# rc-light-controller.net
KiCad netlist of a schematic drawn in EAGLE
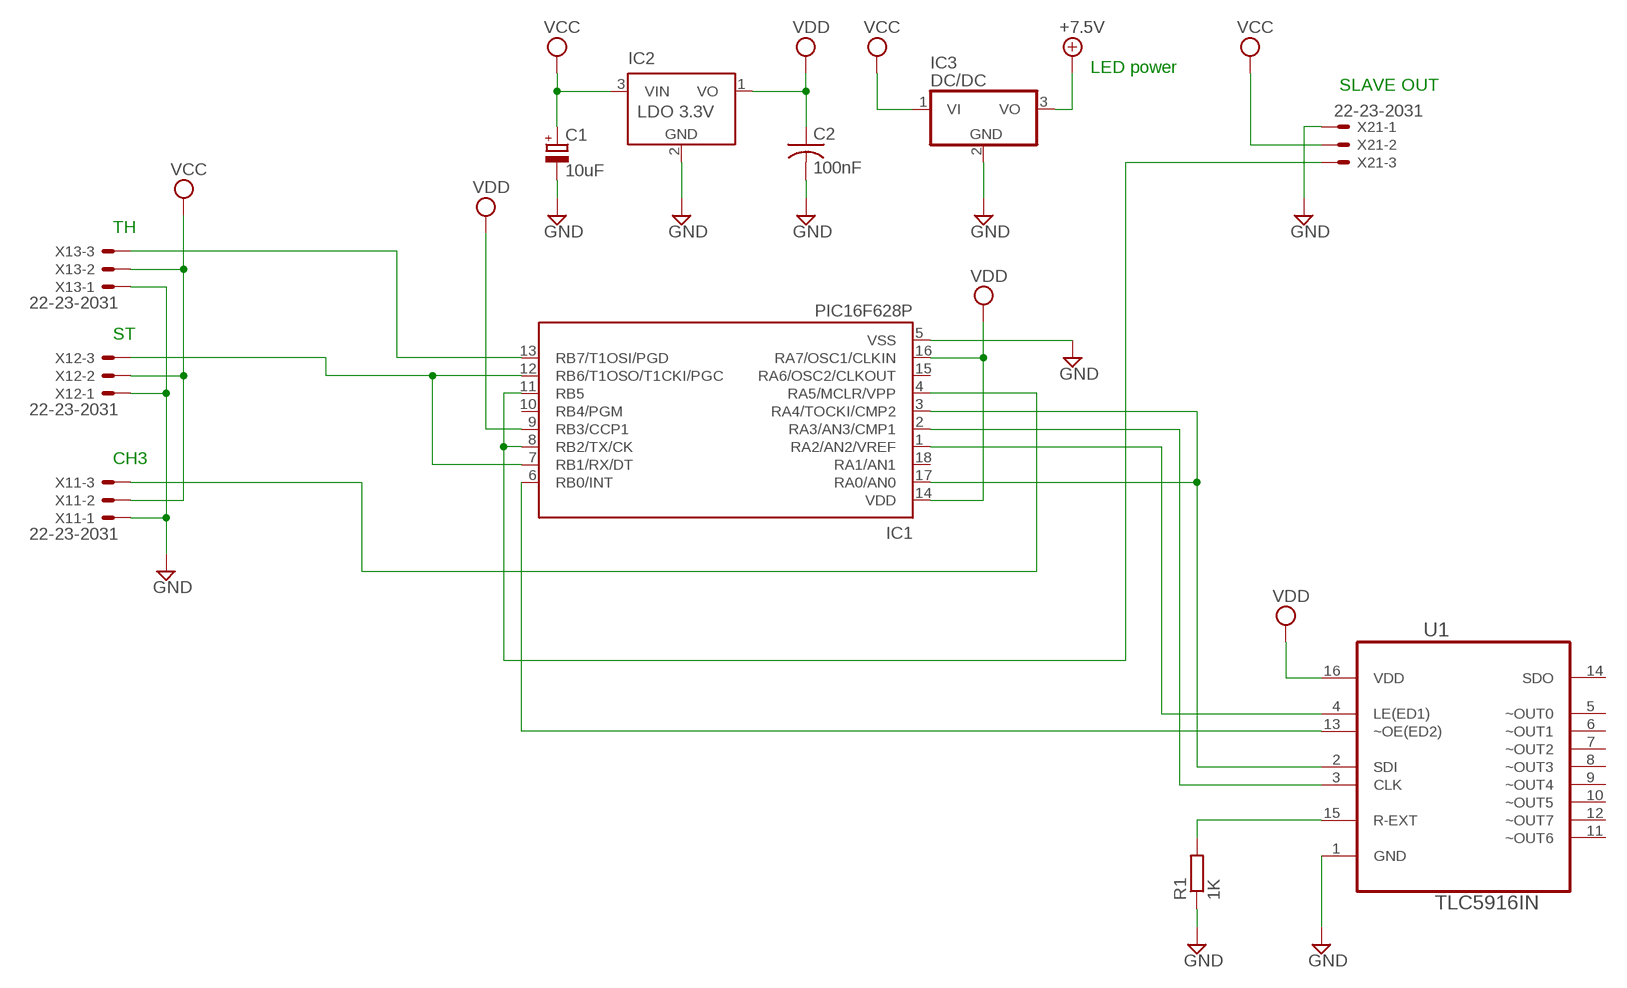
[diagram p0: schematic, sheet 1]

(export (version "E")
  (design (tool "Eeschema 10.0.6"))
  (components
    (comp (ref "C1")
      (value "10uF")
      (footprint "eagle-import:E5-5")
      (libsource (lib "eagle-import") (part "CPOL-EUE5-5"))
    )
    (comp (ref "C2")
      (value "100nF")
      (footprint "eagle-import:C025-025X050")
      (libsource (lib "eagle-import") (part "C-US025-025X050"))
    )
    (comp (ref "IC1")
      (value "PIC16F628P")
      (footprint "eagle-import:DIL18")
      (libsource (lib "eagle-import") (part "PIC16F62P8"))
    )
    (comp (ref "IC2")
      (value "LDO 3.3V")
      (footprint "eagle-import:TO92")
      (fields (field (name "MF") "NATIONAL SEMICONDUCTOR") (field (name "MPN") "LM2936Z-3.3/NOPB"))
      (libsource (lib "eagle-import") (part "LM2936?Z-3.3"))
    )
    (comp (ref "IC3")
      (value "DC/DC")
      (footprint "eagle-import:TO220H")
      (libsource (lib "eagle-import") (part "78T05"))
    )
    (comp (ref "R1")
      (value "1K")
      (footprint "eagle-import:0204_7")
      (libsource (lib "eagle-import") (part "R-EU_0204/7"))
    )
    (comp (ref "U1")
      (value "TLC5916IN")
      (footprint "eagle-import:DIP254P762X508-16")
      (libsource (lib "eagle-import") (part "TLC5916IN"))
    )
    (comp (ref "X11")
      (value "22-23-2031")
      (footprint "eagle-import:22-23-2031")
      (libsource (lib "eagle-import") (part "22-23-2031"))
    )
    (comp (ref "X12")
      (value "22-23-2031")
      (footprint "eagle-import:22-23-2031")
      (libsource (lib "eagle-import") (part "22-23-2031"))
    )
    (comp (ref "X13")
      (value "22-23-2031")
      (footprint "eagle-import:22-23-2031")
      (libsource (lib "eagle-import") (part "22-23-2031"))
    )
    (comp (ref "X21")
      (value "22-23-2031")
      (footprint "eagle-import:22-23-2031")
      (libsource (lib "eagle-import") (part "22-23-2031"))
    )
  )
  (nets
    (net (code "1") (name "+7.5V") (class "Default")
      (node (ref "IC3") (pin "3") (pinfunction "VO_3") (pintype "passive"))
    )
    (net (code "2") (name "GND") (class "Default")
      (node (ref "C1") (pin "-") (pinfunction "-_-") (pintype "passive"))
      (node (ref "C2") (pin "2") (pinfunction "2_2") (pintype "passive"))
      (node (ref "IC1") (pin "5") (pinfunction "VSS_5") (pintype "power_in"))
      (node (ref "IC2") (pin "2") (pinfunction "GND_2") (pintype "passive"))
      (node (ref "IC3") (pin "2") (pinfunction "GND_2") (pintype "passive"))
      (node (ref "R1") (pin "1") (pinfunction "1_1") (pintype "passive"))
      (node (ref "U1") (pin "1") (pinfunction "GND_1") (pintype "passive"))
      (node (ref "X11") (pin "1") (pinfunction "S_1") (pintype "passive"))
      (node (ref "X12") (pin "1") (pinfunction "S_1") (pintype "passive"))
      (node (ref "X13") (pin "1") (pinfunction "S_1") (pintype "passive"))
      (node (ref "X21") (pin "1") (pinfunction "S_1") (pintype "passive"))
    )
    (net (code "3") (name "Net-(IC1-RA0{slash}AN0)") (class "Default")
      (node (ref "IC1") (pin "17") (pinfunction "RA0/AN0_17") (pintype "bidirectional"))
      (node (ref "IC1") (pin "3") (pinfunction "RA4/TOCKI/CMP2_3") (pintype "bidirectional"))
      (node (ref "U1") (pin "2") (pinfunction "SDI_2") (pintype "input"))
    )
    (net (code "4") (name "Net-(IC1-RA2{slash}AN2{slash}VREF)") (class "Default")
      (node (ref "IC1") (pin "1") (pinfunction "RA2/AN2/VREF_1") (pintype "bidirectional"))
      (node (ref "U1") (pin "4") (pinfunction "LE(ED1)_4") (pintype "input"))
    )
    (net (code "5") (name "Net-(IC1-RA3{slash}AN3{slash}CMP1)") (class "Default")
      (node (ref "IC1") (pin "2") (pinfunction "RA3/AN3/CMP1_2") (pintype "bidirectional"))
      (node (ref "U1") (pin "3") (pinfunction "CLK_3") (pintype "input"))
    )
    (net (code "6") (name "Net-(IC1-RA5{slash}MCLR{slash}VPP)") (class "Default")
      (node (ref "IC1") (pin "4") (pinfunction "RA5/MCLR/VPP_4") (pintype "bidirectional"))
      (node (ref "X11") (pin "3") (pinfunction "S_3") (pintype "passive"))
    )
    (net (code "7") (name "Net-(IC1-RB0{slash}INT)") (class "Default")
      (node (ref "IC1") (pin "6") (pinfunction "RB0/INT_6") (pintype "bidirectional"))
      (node (ref "U1") (pin "13") (pinfunction "~{OE(ED2})_13") (pintype "input"))
    )
    (net (code "8") (name "Net-(IC1-RB1{slash}RX{slash}DT)") (class "Default")
      (node (ref "IC1") (pin "12") (pinfunction "RB6/T1OSO/T1CKI/PGC_12") (pintype "bidirectional"))
      (node (ref "IC1") (pin "7") (pinfunction "RB1/RX/DT_7") (pintype "bidirectional"))
      (node (ref "X12") (pin "3") (pinfunction "S_3") (pintype "passive"))
    )
    (net (code "9") (name "Net-(IC1-RB2{slash}TX{slash}CK)") (class "Default")
      (node (ref "IC1") (pin "11") (pinfunction "RB5_11") (pintype "bidirectional"))
      (node (ref "IC1") (pin "8") (pinfunction "RB2/TX/CK_8") (pintype "bidirectional"))
      (node (ref "X21") (pin "3") (pinfunction "S_3") (pintype "passive"))
    )
    (net (code "10") (name "Net-(IC1-RB7{slash}T1OSI{slash}PGD)") (class "Default")
      (node (ref "IC1") (pin "13") (pinfunction "RB7/T1OSI/PGD_13") (pintype "bidirectional"))
      (node (ref "X13") (pin "3") (pinfunction "S_3") (pintype "passive"))
    )
    (net (code "11") (name "Net-(U1-R-EXT)") (class "Default")
      (node (ref "R1") (pin "2") (pinfunction "2_2") (pintype "passive"))
      (node (ref "U1") (pin "15") (pinfunction "R-EXT_15") (pintype "passive"))
    )
    (net (code "12") (name "VCC") (class "Default")
      (node (ref "C1") (pin "+") (pinfunction "+_+") (pintype "passive"))
      (node (ref "IC2") (pin "3") (pinfunction "VIN_3") (pintype "input"))
      (node (ref "IC3") (pin "1") (pinfunction "VI_1") (pintype "input"))
      (node (ref "X11") (pin "2") (pinfunction "S_2") (pintype "passive"))
      (node (ref "X12") (pin "2") (pinfunction "S_2") (pintype "passive"))
      (node (ref "X13") (pin "2") (pinfunction "S_2") (pintype "passive"))
      (node (ref "X21") (pin "2") (pinfunction "S_2") (pintype "passive"))
    )
    (net (code "13") (name "VDD") (class "Default")
      (node (ref "C2") (pin "1") (pinfunction "1_1") (pintype "passive"))
      (node (ref "IC1") (pin "14") (pinfunction "VDD_14") (pintype "power_in"))
      (node (ref "IC1") (pin "16") (pinfunction "RA7/OSC1/CLKIN_16") (pintype "bidirectional"))
      (node (ref "IC1") (pin "9") (pinfunction "RB3/CCP1_9") (pintype "bidirectional"))
      (node (ref "IC2") (pin "1") (pinfunction "VO_1") (pintype "passive"))
      (node (ref "U1") (pin "16") (pinfunction "VDD_16") (pintype "power_in"))
    )
    (net (code "14") (name "unconnected-(IC1-RA1{slash}AN1-Pad18)") (class "Default")
      (node (ref "IC1") (pin "18") (pinfunction "RA1/AN1_18") (pintype "bidirectional"))
    )
    (net (code "15") (name "unconnected-(IC1-RA6{slash}OSC2{slash}CLKOUT-Pad15)") (class "Default")
      (node (ref "IC1") (pin "15") (pinfunction "RA6/OSC2/CLKOUT_15") (pintype "bidirectional"))
    )
    (net (code "16") (name "unconnected-(IC1-RB4{slash}PGM-Pad10)") (class "Default")
      (node (ref "IC1") (pin "10") (pinfunction "RB4/PGM_10") (pintype "bidirectional"))
    )
    (net (code "17") (name "unconnected-(U1-SDO-Pad14)") (class "Default")
      (node (ref "U1") (pin "14") (pinfunction "SDO_14") (pintype "output"))
    )
    (net (code "18") (name "unconnected-(U1-~{OUT0}-Pad5)") (class "Default")
      (node (ref "U1") (pin "5") (pinfunction "~{OUT0}_5") (pintype "output"))
    )
    (net (code "19") (name "unconnected-(U1-~{OUT1}-Pad6)") (class "Default")
      (node (ref "U1") (pin "6") (pinfunction "~{OUT1}_6") (pintype "output"))
    )
    (net (code "20") (name "unconnected-(U1-~{OUT2}-Pad7)") (class "Default")
      (node (ref "U1") (pin "7") (pinfunction "~{OUT2}_7") (pintype "output"))
    )
    (net (code "21") (name "unconnected-(U1-~{OUT3}-Pad8)") (class "Default")
      (node (ref "U1") (pin "8") (pinfunction "~{OUT3}_8") (pintype "output"))
    )
    (net (code "22") (name "unconnected-(U1-~{OUT4}-Pad9)") (class "Default")
      (node (ref "U1") (pin "9") (pinfunction "~{OUT4}_9") (pintype "output"))
    )
    (net (code "23") (name "unconnected-(U1-~{OUT5}-Pad10)") (class "Default")
      (node (ref "U1") (pin "10") (pinfunction "~{OUT5}_10") (pintype "output"))
    )
    (net (code "24") (name "unconnected-(U1-~{OUT6}-Pad11)") (class "Default")
      (node (ref "U1") (pin "11") (pinfunction "~{OUT6}_11") (pintype "output"))
    )
    (net (code "25") (name "unconnected-(U1-~{OUT7}-Pad12)") (class "Default")
      (node (ref "U1") (pin "12") (pinfunction "~{OUT7}_12") (pintype "output"))
    )
  )
)
